# BlueBird_Sch.net
KiCad netlist of a schematic drawn in EAGLE
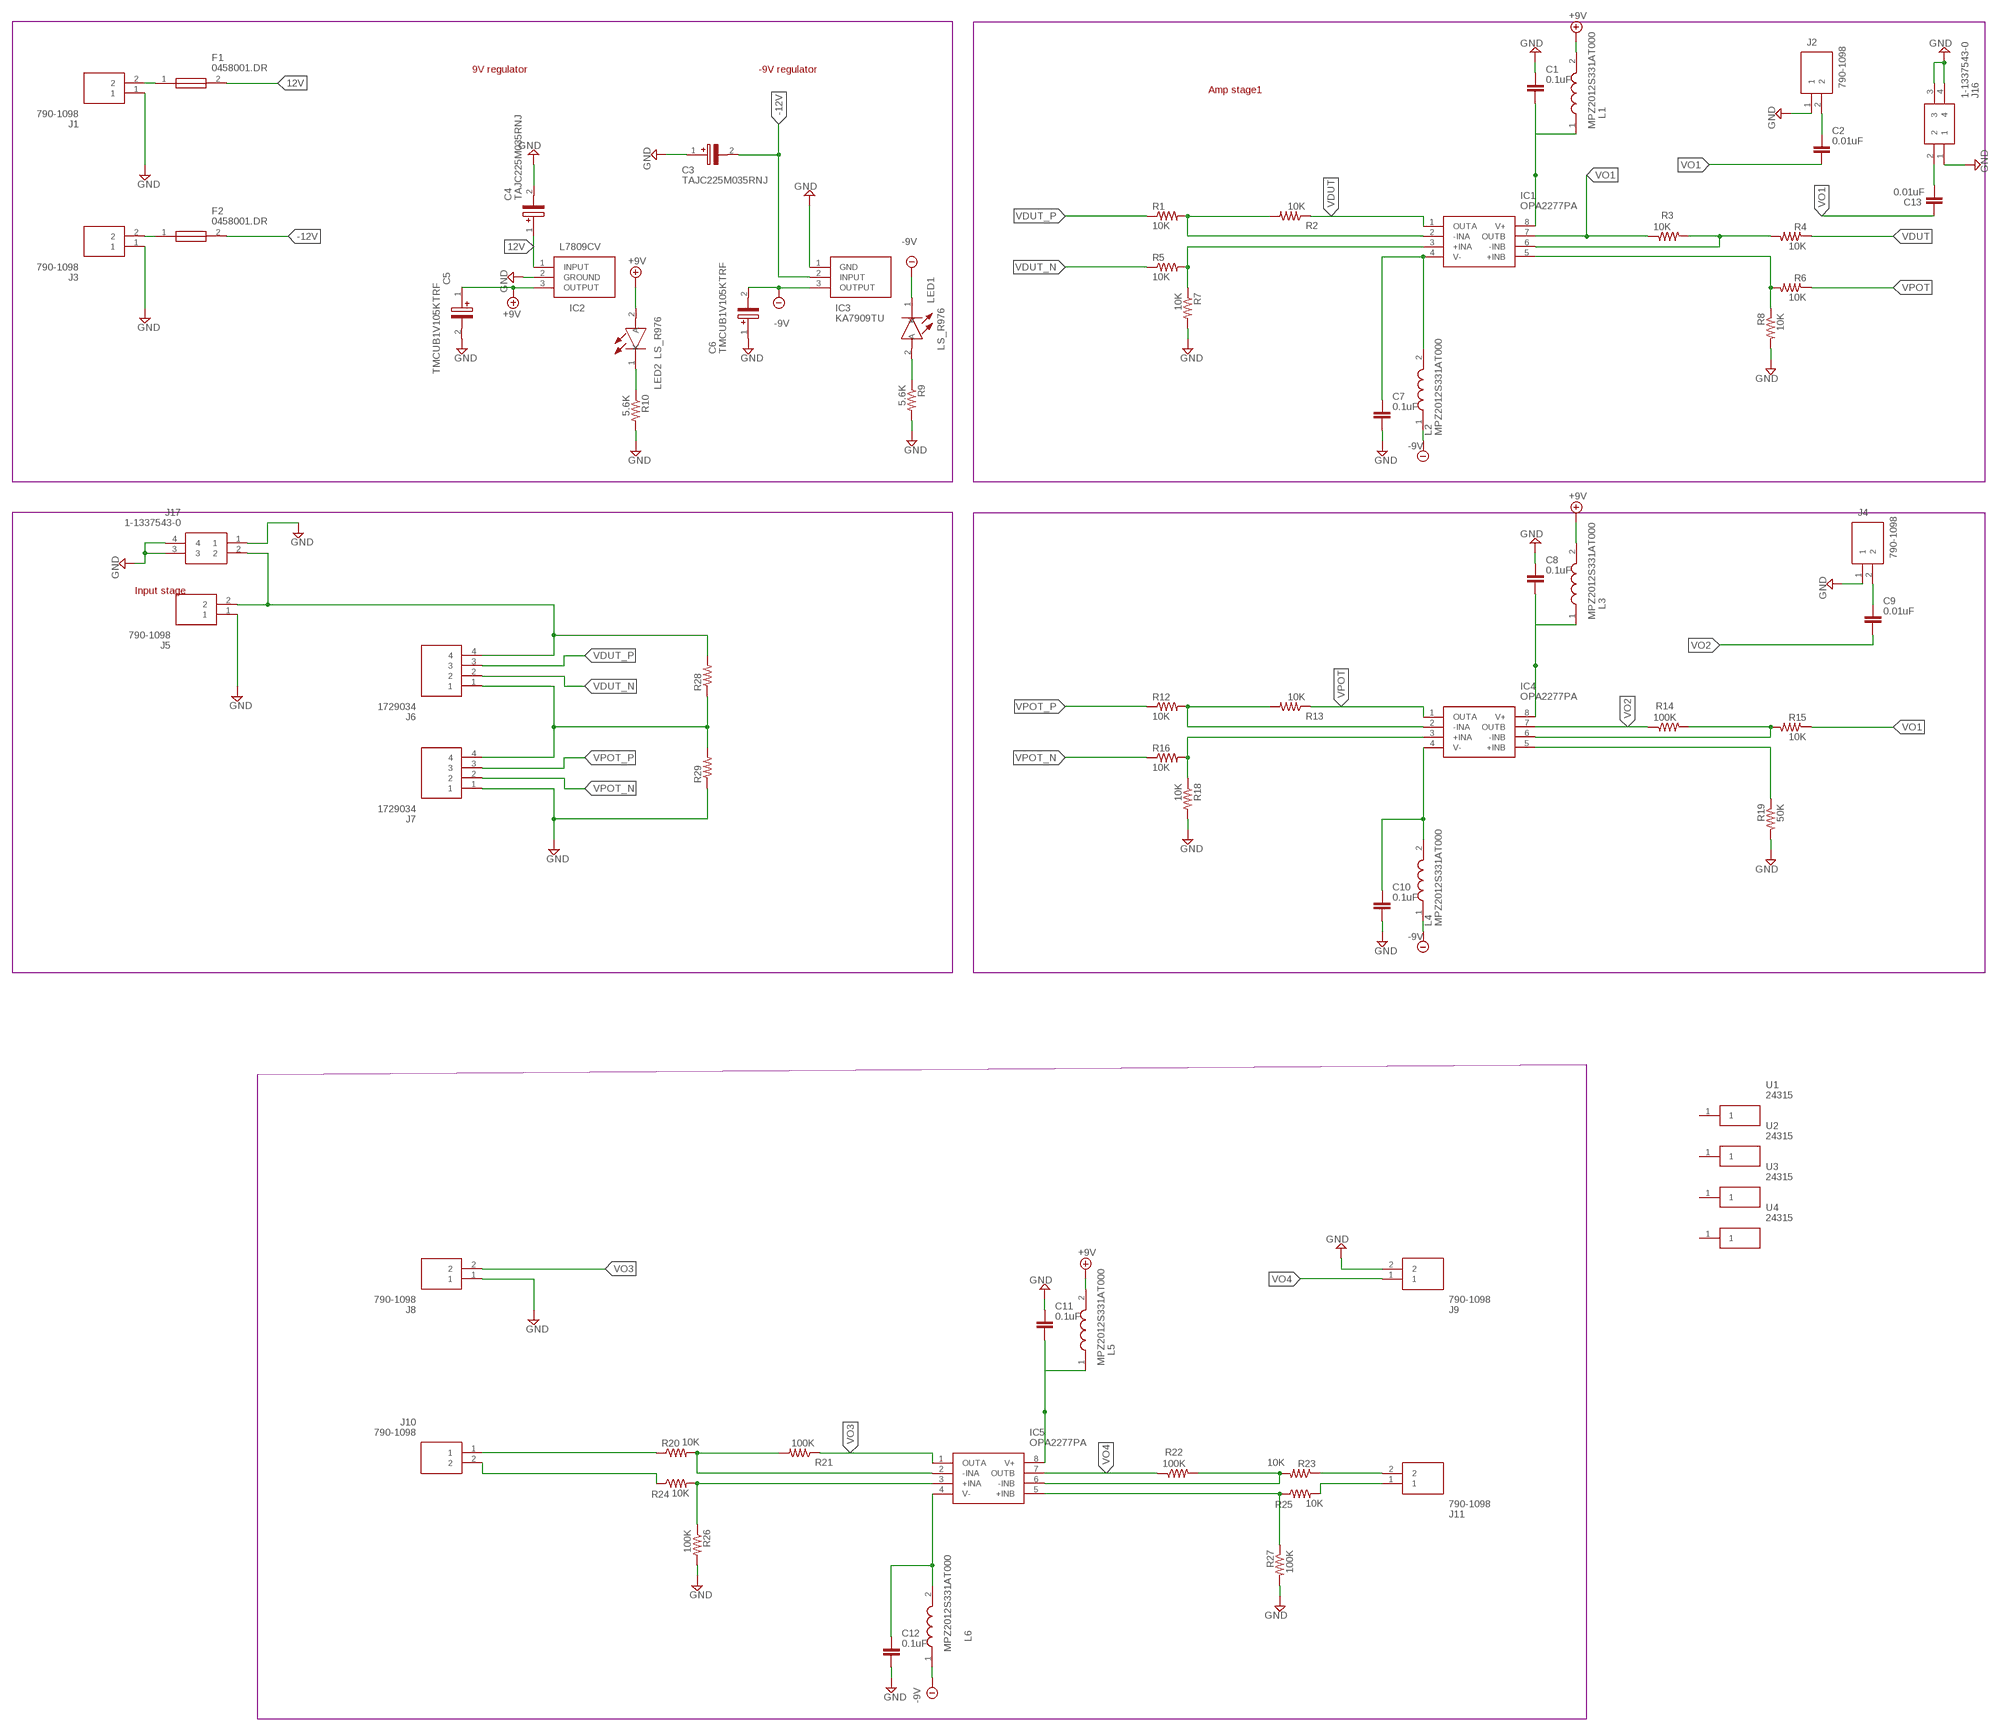
[diagram p0: schematic, sheet 1]

(export (version "E")
  (design (tool "Eeschema 10.0.6"))
  (components
    (comp (ref "C1")
      (value "0.1uF")
      (footprint "eagle-import:CAPC2012X110")
      (libsource (lib "eagle-import") (part "CCHIP-0805(2012-METRIC)_"))
    )
    (comp (ref "C2")
      (value "0.01uF")
      (footprint "eagle-import:CAPC2012X110")
      (libsource (lib "eagle-import") (part "CCHIP-0805(2012-METRIC)_"))
    )
    (comp (ref "C3")
      (value "TAJC225M035RNJ")
      (footprint "eagle-import:CAPPM6032X280N")
      (fields (field (name "RS_PART_NUMBER") "1364458P"))
      (libsource (lib "eagle-import") (part "TAJC225M035RNJ"))
    )
    (comp (ref "C4")
      (value "TAJC225M035RNJ")
      (footprint "eagle-import:CAPPM6032X280N")
      (fields (field (name "RS_PART_NUMBER") "1364458P"))
      (libsource (lib "eagle-import") (part "TAJC225M035RNJ"))
    )
    (comp (ref "C5")
      (value "TMCUB1V105KTRF")
      (footprint "eagle-import:CAPPM3528X120N")
      (fields (field (name "RS_PART_NUMBER") "1882061"))
      (libsource (lib "eagle-import") (part "TMCUB1V105KTRF"))
    )
    (comp (ref "C6")
      (value "TMCUB1V105KTRF")
      (footprint "eagle-import:CAPPM3528X120N")
      (fields (field (name "RS_PART_NUMBER") "1882061"))
      (libsource (lib "eagle-import") (part "TMCUB1V105KTRF"))
    )
    (comp (ref "C7")
      (value "0.1uF")
      (footprint "eagle-import:CAPC2012X110")
      (libsource (lib "eagle-import") (part "CCHIP-0805(2012-METRIC)_"))
    )
    (comp (ref "C8")
      (value "0.1uF")
      (footprint "eagle-import:CAPC2012X110")
      (libsource (lib "eagle-import") (part "CCHIP-0805(2012-METRIC)_"))
    )
    (comp (ref "C9")
      (value "0.01uF")
      (footprint "eagle-import:CAPC2012X110")
      (libsource (lib "eagle-import") (part "CCHIP-0805(2012-METRIC)_"))
    )
    (comp (ref "C10")
      (value "0.1uF")
      (footprint "eagle-import:CAPC2012X110")
      (libsource (lib "eagle-import") (part "CCHIP-0805(2012-METRIC)_"))
    )
    (comp (ref "C11")
      (value "0.1uF")
      (footprint "eagle-import:CAPC2012X110")
      (libsource (lib "eagle-import") (part "CCHIP-0805(2012-METRIC)_"))
    )
    (comp (ref "C12")
      (value "0.1uF")
      (footprint "eagle-import:CAPC2012X110")
      (libsource (lib "eagle-import") (part "CCHIP-0805(2012-METRIC)_"))
    )
    (comp (ref "C13")
      (value "0.01uF")
      (footprint "eagle-import:CAPC2012X110")
      (libsource (lib "eagle-import") (part "CCHIP-0805(2012-METRIC)_"))
    )
    (comp (ref "F1")
      (value "0458001.DR")
      (footprint "eagle-import:FUSC3215X58N")
      (libsource (lib "eagle-import") (part "0458001.DR"))
    )
    (comp (ref "F2")
      (value "0458001.DR")
      (footprint "eagle-import:FUSC3215X58N")
      (libsource (lib "eagle-import") (part "0458001.DR"))
    )
    (comp (ref "IC1")
      (value "OPA2277PA")
      (footprint "eagle-import:DIP794W53P254L959H508Q8N")
      (fields (field (name "RS_PART_NUMBER") "3071673P"))
      (libsource (lib "eagle-import") (part "OPA2277PA"))
    )
    (comp (ref "IC2")
      (value "L7809CV")
      (footprint "eagle-import:TO255P460X1020X2008-3P")
      (fields (field (name "RS_PART_NUMBER") "7140666P"))
      (libsource (lib "eagle-import") (part "L7809CV"))
    )
    (comp (ref "IC3")
      (value "KA7909TU")
      (footprint "eagle-import:TO254P470X1016X2019-3P")
      (fields (field (name "RS_PART_NUMBER") "7390552P"))
      (libsource (lib "eagle-import") (part "KA7909TU"))
    )
    (comp (ref "IC4")
      (value "OPA2277PA")
      (footprint "eagle-import:DIP794W53P254L959H508Q8N")
      (fields (field (name "RS_PART_NUMBER") "3071673P"))
      (libsource (lib "eagle-import") (part "OPA2277PA"))
    )
    (comp (ref "IC5")
      (value "OPA2277PA")
      (footprint "eagle-import:DIP794W53P254L959H508Q8N")
      (fields (field (name "RS_PART_NUMBER") "3071673P"))
      (libsource (lib "eagle-import") (part "OPA2277PA"))
    )
    (comp (ref "J1")
      (value "790-1098")
      (footprint "eagle-import:7901098")
      (libsource (lib "eagle-import") (part "790-1098"))
    )
    (comp (ref "J2")
      (value "790-1098")
      (footprint "eagle-import:7901098")
      (libsource (lib "eagle-import") (part "790-1098"))
    )
    (comp (ref "J3")
      (value "790-1098")
      (footprint "eagle-import:7901098")
      (libsource (lib "eagle-import") (part "790-1098"))
    )
    (comp (ref "J4")
      (value "790-1098")
      (footprint "eagle-import:7901098")
      (libsource (lib "eagle-import") (part "790-1098"))
    )
    (comp (ref "J5")
      (value "790-1098")
      (footprint "eagle-import:7901098")
      (libsource (lib "eagle-import") (part "790-1098"))
    )
    (comp (ref "J6")
      (value "1729034")
      (footprint "eagle-import:SHDR4W110P0X500_1X4_2000X810X1")
      (fields (field (name "RS_PART_NUMBER") "8020620"))
      (libsource (lib "eagle-import") (part "1729034"))
    )
    (comp (ref "J7")
      (value "1729034")
      (footprint "eagle-import:SHDR4W110P0X500_1X4_2000X810X1")
      (fields (field (name "RS_PART_NUMBER") "8020620"))
      (libsource (lib "eagle-import") (part "1729034"))
    )
    (comp (ref "J8")
      (value "790-1098")
      (footprint "eagle-import:7901098")
      (libsource (lib "eagle-import") (part "790-1098"))
    )
    (comp (ref "J9")
      (value "790-1098")
      (footprint "eagle-import:7901098")
      (libsource (lib "eagle-import") (part "790-1098"))
    )
    (comp (ref "J10")
      (value "790-1098")
      (footprint "eagle-import:7901098")
      (libsource (lib "eagle-import") (part "790-1098"))
    )
    (comp (ref "J11")
      (value "790-1098")
      (footprint "eagle-import:7901098")
      (libsource (lib "eagle-import") (part "790-1098"))
    )
    (comp (ref "J16")
      (value "1-1337543-0")
      (footprint "eagle-import:1-1337543-0")
      (fields (field (name "RS_PART_NUMBER") "5121225P"))
      (libsource (lib "eagle-import") (part "1-1337543-0"))
    )
    (comp (ref "J17")
      (value "1-1337543-0")
      (footprint "eagle-import:1-1337543-0")
      (fields (field (name "RS_PART_NUMBER") "5121225P"))
      (libsource (lib "eagle-import") (part "1-1337543-0"))
    )
    (comp (ref "L1")
      (value "MPZ2012S331AT000")
      (footprint "eagle-import:INDC2012X105N")
      (libsource (lib "eagle-import") (part "MPZ2012S331AT000"))
    )
    (comp (ref "L2")
      (value "MPZ2012S331AT000")
      (footprint "eagle-import:INDC2012X105N")
      (libsource (lib "eagle-import") (part "MPZ2012S331AT000"))
    )
    (comp (ref "L3")
      (value "MPZ2012S331AT000")
      (footprint "eagle-import:INDC2012X105N")
      (libsource (lib "eagle-import") (part "MPZ2012S331AT000"))
    )
    (comp (ref "L4")
      (value "MPZ2012S331AT000")
      (footprint "eagle-import:INDC2012X105N")
      (libsource (lib "eagle-import") (part "MPZ2012S331AT000"))
    )
    (comp (ref "L5")
      (value "MPZ2012S331AT000")
      (footprint "eagle-import:INDC2012X105N")
      (libsource (lib "eagle-import") (part "MPZ2012S331AT000"))
    )
    (comp (ref "L6")
      (value "MPZ2012S331AT000")
      (footprint "eagle-import:INDC2012X105N")
      (libsource (lib "eagle-import") (part "MPZ2012S331AT000"))
    )
    (comp (ref "LED1")
      (value "LS_R976")
      (footprint "eagle-import:LEDC2012X40N")
      (fields (field (name "MANUFACTURER_PART_NUMBER") "LS R976") (field (name "RS_PART_NUMBER") "4974804P"))
      (libsource (lib "eagle-import") (part "LS_R976"))
    )
    (comp (ref "LED2")
      (value "LS_R976")
      (footprint "eagle-import:LEDC2012X40N")
      (fields (field (name "MANUFACTURER_PART_NUMBER") "LS R976") (field (name "RS_PART_NUMBER") "4974804P"))
      (libsource (lib "eagle-import") (part "LS_R976"))
    )
    (comp (ref "R1")
      (value "10K")
      (footprint "eagle-import:R0805")
      (libsource (lib "eagle-import") (part "R-US_R0805"))
    )
    (comp (ref "R2")
      (value "10K")
      (footprint "eagle-import:R0805")
      (libsource (lib "eagle-import") (part "R-US_R0805"))
    )
    (comp (ref "R3")
      (value "10K")
      (footprint "eagle-import:R0805")
      (libsource (lib "eagle-import") (part "R-US_R0805"))
    )
    (comp (ref "R4")
      (value "10K")
      (footprint "eagle-import:R0805")
      (libsource (lib "eagle-import") (part "R-US_R0805"))
    )
    (comp (ref "R5")
      (value "10K")
      (footprint "eagle-import:R0805")
      (libsource (lib "eagle-import") (part "R-US_R0805"))
    )
    (comp (ref "R6")
      (value "10K")
      (footprint "eagle-import:R0805")
      (libsource (lib "eagle-import") (part "R-US_R0805"))
    )
    (comp (ref "R7")
      (value "10K")
      (footprint "eagle-import:R0805")
      (libsource (lib "eagle-import") (part "R-US_R0805"))
    )
    (comp (ref "R8")
      (value "10K")
      (footprint "eagle-import:R0805")
      (libsource (lib "eagle-import") (part "R-US_R0805"))
    )
    (comp (ref "R9")
      (value "5.6K")
      (footprint "eagle-import:R0805")
      (libsource (lib "eagle-import") (part "R-US_R0805"))
    )
    (comp (ref "R10")
      (value "5.6K")
      (footprint "eagle-import:R0805")
      (libsource (lib "eagle-import") (part "R-US_R0805"))
    )
    (comp (ref "R12")
      (value "10K")
      (footprint "eagle-import:R0805")
      (libsource (lib "eagle-import") (part "R-US_R0805"))
    )
    (comp (ref "R13")
      (value "10K")
      (footprint "eagle-import:R0805")
      (libsource (lib "eagle-import") (part "R-US_R0805"))
    )
    (comp (ref "R14")
      (value "100K")
      (footprint "eagle-import:R0805")
      (libsource (lib "eagle-import") (part "R-US_R0805"))
    )
    (comp (ref "R15")
      (value "10K")
      (footprint "eagle-import:R0805")
      (libsource (lib "eagle-import") (part "R-US_R0805"))
    )
    (comp (ref "R16")
      (value "10K")
      (footprint "eagle-import:R0805")
      (libsource (lib "eagle-import") (part "R-US_R0805"))
    )
    (comp (ref "R18")
      (value "10K")
      (footprint "eagle-import:R0805")
      (libsource (lib "eagle-import") (part "R-US_R0805"))
    )
    (comp (ref "R19")
      (value "50K")
      (footprint "eagle-import:R0805")
      (libsource (lib "eagle-import") (part "R-US_R0805"))
    )
    (comp (ref "R20")
      (value "10K")
      (footprint "eagle-import:R0805")
      (libsource (lib "eagle-import") (part "R-US_R0805"))
    )
    (comp (ref "R21")
      (value "100K")
      (footprint "eagle-import:R0805")
      (libsource (lib "eagle-import") (part "R-US_R0805"))
    )
    (comp (ref "R22")
      (value "100K")
      (footprint "eagle-import:R0805")
      (libsource (lib "eagle-import") (part "R-US_R0805"))
    )
    (comp (ref "R23")
      (value "10K")
      (footprint "eagle-import:R0805")
      (libsource (lib "eagle-import") (part "R-US_R0805"))
    )
    (comp (ref "R24")
      (value "10K")
      (footprint "eagle-import:R0805")
      (libsource (lib "eagle-import") (part "R-US_R0805"))
    )
    (comp (ref "R25")
      (value "10K")
      (footprint "eagle-import:R0805")
      (libsource (lib "eagle-import") (part "R-US_R0805"))
    )
    (comp (ref "R26")
      (value "100K")
      (footprint "eagle-import:R0805")
      (libsource (lib "eagle-import") (part "R-US_R0805"))
    )
    (comp (ref "R27")
      (value "100K")
      (footprint "eagle-import:R0805")
      (libsource (lib "eagle-import") (part "R-US_R0805"))
    )
    (comp (ref "R28")
      (value "R-US_R1206")
      (footprint "eagle-import:R1206")
      (libsource (lib "eagle-import") (part "R-US_R1206"))
    )
    (comp (ref "R29")
      (value "R-US_R1206")
      (footprint "eagle-import:R1206")
      (libsource (lib "eagle-import") (part "R-US_R1206"))
    )
    (comp (ref "U1")
      (value "24315")
      (footprint "eagle-import:24315")
      (libsource (lib "eagle-import") (part "24315"))
    )
    (comp (ref "U2")
      (value "24315")
      (footprint "eagle-import:24315")
      (libsource (lib "eagle-import") (part "24315"))
    )
    (comp (ref "U3")
      (value "24315")
      (footprint "eagle-import:24315")
      (libsource (lib "eagle-import") (part "24315"))
    )
    (comp (ref "U4")
      (value "24315")
      (footprint "eagle-import:24315")
      (libsource (lib "eagle-import") (part "24315"))
    )
  )
  (nets
    (net (code "1") (name "+9V") (class "Default")
      (node (ref "C5") (pin "1") (pinfunction "+_1") (pintype "bidirectional"))
      (node (ref "IC2") (pin "3") (pinfunction "OUTPUT_3") (pintype "bidirectional"))
      (node (ref "L1") (pin "2") (pinfunction "2_2") (pintype "bidirectional"))
      (node (ref "L3") (pin "2") (pinfunction "2_2") (pintype "bidirectional"))
      (node (ref "L5") (pin "2") (pinfunction "2_2") (pintype "bidirectional"))
      (node (ref "LED2") (pin "2") (pinfunction "A_2") (pintype "bidirectional"))
    )
    (net (code "2") (name "-9V") (class "Default")
      (node (ref "C6") (pin "2") (pinfunction "-_2") (pintype "bidirectional"))
      (node (ref "IC3") (pin "3") (pinfunction "OUTPUT_3") (pintype "bidirectional"))
      (node (ref "L2") (pin "1") (pinfunction "1_1") (pintype "bidirectional"))
      (node (ref "L4") (pin "1") (pinfunction "1_1") (pintype "bidirectional"))
      (node (ref "L6") (pin "1") (pinfunction "1_1") (pintype "bidirectional"))
      (node (ref "LED1") (pin "1") (pinfunction "K_1") (pintype "bidirectional"))
    )
    (net (code "3") (name "-12V") (class "Default")
      (node (ref "C3") (pin "2") (pinfunction "-_2") (pintype "bidirectional"))
      (node (ref "F2") (pin "2") (pinfunction "2_2") (pintype "bidirectional"))
      (node (ref "IC3") (pin "2") (pinfunction "INPUT_2") (pintype "bidirectional"))
    )
    (net (code "4") (name "12V") (class "Default")
      (node (ref "C4") (pin "1") (pinfunction "+_1") (pintype "bidirectional"))
      (node (ref "F1") (pin "2") (pinfunction "2_2") (pintype "bidirectional"))
      (node (ref "IC2") (pin "1") (pinfunction "INPUT_1") (pintype "bidirectional"))
    )
    (net (code "5") (name "GND") (class "Default")
      (node (ref "C1") (pin "1") (pinfunction "1_1") (pintype "passive"))
      (node (ref "C10") (pin "2") (pinfunction "2_2") (pintype "passive"))
      (node (ref "C11") (pin "1") (pinfunction "1_1") (pintype "passive"))
      (node (ref "C12") (pin "2") (pinfunction "2_2") (pintype "passive"))
      (node (ref "C3") (pin "1") (pinfunction "+_1") (pintype "bidirectional"))
      (node (ref "C4") (pin "2") (pinfunction "-_2") (pintype "bidirectional"))
      (node (ref "C5") (pin "2") (pinfunction "-_2") (pintype "bidirectional"))
      (node (ref "C6") (pin "1") (pinfunction "+_1") (pintype "bidirectional"))
      (node (ref "C7") (pin "2") (pinfunction "2_2") (pintype "passive"))
      (node (ref "C8") (pin "1") (pinfunction "1_1") (pintype "passive"))
      (node (ref "IC2") (pin "2") (pinfunction "GROUND_2") (pintype "bidirectional"))
      (node (ref "IC3") (pin "1") (pinfunction "GND_1") (pintype "bidirectional"))
      (node (ref "J1") (pin "1") (pinfunction "1_1") (pintype "bidirectional"))
      (node (ref "J16") (pin "1") (pinfunction "1_1") (pintype "bidirectional"))
      (node (ref "J16") (pin "3") (pinfunction "3_3") (pintype "bidirectional"))
      (node (ref "J16") (pin "4") (pinfunction "4_4") (pintype "bidirectional"))
      (node (ref "J17") (pin "1") (pinfunction "1_1") (pintype "bidirectional"))
      (node (ref "J17") (pin "3") (pinfunction "3_3") (pintype "bidirectional"))
      (node (ref "J17") (pin "4") (pinfunction "4_4") (pintype "bidirectional"))
      (node (ref "J2") (pin "1") (pinfunction "1_1") (pintype "bidirectional"))
      (node (ref "J3") (pin "1") (pinfunction "1_1") (pintype "bidirectional"))
      (node (ref "J4") (pin "1") (pinfunction "1_1") (pintype "bidirectional"))
      (node (ref "J5") (pin "1") (pinfunction "1_1") (pintype "bidirectional"))
      (node (ref "J7") (pin "1") (pinfunction "1_1") (pintype "bidirectional"))
      (node (ref "J8") (pin "1") (pinfunction "1_1") (pintype "bidirectional"))
      (node (ref "J9") (pin "2") (pinfunction "2_2") (pintype "bidirectional"))
      (node (ref "R10") (pin "2") (pinfunction "2_2") (pintype "passive"))
      (node (ref "R18") (pin "2") (pinfunction "2_2") (pintype "passive"))
      (node (ref "R19") (pin "2") (pinfunction "2_2") (pintype "passive"))
      (node (ref "R26") (pin "2") (pinfunction "2_2") (pintype "passive"))
      (node (ref "R27") (pin "2") (pinfunction "2_2") (pintype "passive"))
      (node (ref "R29") (pin "1") (pinfunction "1_1") (pintype "passive"))
      (node (ref "R7") (pin "2") (pinfunction "2_2") (pintype "passive"))
      (node (ref "R8") (pin "2") (pinfunction "2_2") (pintype "passive"))
      (node (ref "R9") (pin "2") (pinfunction "2_2") (pintype "passive"))
    )
    (net (code "6") (name "Net-(C2-Pad1)") (class "Default")
      (node (ref "C2") (pin "1") (pinfunction "1_1") (pintype "passive"))
      (node (ref "J2") (pin "2") (pinfunction "2_2") (pintype "bidirectional"))
    )
    (net (code "7") (name "Net-(C9-Pad1)") (class "Default")
      (node (ref "C9") (pin "1") (pinfunction "1_1") (pintype "passive"))
      (node (ref "J4") (pin "2") (pinfunction "2_2") (pintype "bidirectional"))
    )
    (net (code "8") (name "Net-(C13-Pad1)") (class "Default")
      (node (ref "C13") (pin "1") (pinfunction "1_1") (pintype "passive"))
      (node (ref "J16") (pin "2") (pinfunction "2_2") (pintype "bidirectional"))
    )
    (net (code "9") (name "Net-(F1-Pad1)") (class "Default")
      (node (ref "F1") (pin "1") (pinfunction "1_1") (pintype "bidirectional"))
      (node (ref "J1") (pin "2") (pinfunction "2_2") (pintype "bidirectional"))
    )
    (net (code "10") (name "Net-(F2-Pad1)") (class "Default")
      (node (ref "F2") (pin "1") (pinfunction "1_1") (pintype "bidirectional"))
      (node (ref "J3") (pin "2") (pinfunction "2_2") (pintype "bidirectional"))
    )
    (net (code "11") (name "Net-(IC1-+INA)") (class "Default")
      (node (ref "IC1") (pin "3") (pinfunction "+INA_3") (pintype "input"))
      (node (ref "R5") (pin "2") (pinfunction "2_2") (pintype "passive"))
      (node (ref "R7") (pin "1") (pinfunction "1_1") (pintype "passive"))
    )
    (net (code "12") (name "Net-(IC1-+INB)") (class "Default")
      (node (ref "IC1") (pin "5") (pinfunction "+INB_5") (pintype "input"))
      (node (ref "R6") (pin "2") (pinfunction "2_2") (pintype "passive"))
      (node (ref "R8") (pin "1") (pinfunction "1_1") (pintype "passive"))
    )
    (net (code "13") (name "Net-(IC1--INA)") (class "Default")
      (node (ref "IC1") (pin "2") (pinfunction "-INA_2") (pintype "input"))
      (node (ref "R1") (pin "2") (pinfunction "2_2") (pintype "passive"))
      (node (ref "R2") (pin "2") (pinfunction "2_2") (pintype "passive"))
    )
    (net (code "14") (name "Net-(IC1--INB)") (class "Default")
      (node (ref "IC1") (pin "6") (pinfunction "-INB_6") (pintype "input"))
      (node (ref "R3") (pin "2") (pinfunction "2_2") (pintype "passive"))
      (node (ref "R4") (pin "2") (pinfunction "2_2") (pintype "passive"))
    )
    (net (code "15") (name "Net-(IC1-V+)") (class "Default")
      (node (ref "C1") (pin "2") (pinfunction "2_2") (pintype "passive"))
      (node (ref "IC1") (pin "8") (pinfunction "V+_8") (pintype "power_in"))
      (node (ref "L1") (pin "1") (pinfunction "1_1") (pintype "bidirectional"))
    )
    (net (code "16") (name "Net-(IC1-V-)") (class "Default")
      (node (ref "C7") (pin "1") (pinfunction "1_1") (pintype "passive"))
      (node (ref "IC1") (pin "4") (pinfunction "V-_4") (pintype "power_in"))
      (node (ref "L2") (pin "2") (pinfunction "2_2") (pintype "bidirectional"))
    )
    (net (code "17") (name "Net-(IC4-+INA)") (class "Default")
      (node (ref "IC4") (pin "3") (pinfunction "+INA_3") (pintype "input"))
      (node (ref "R16") (pin "2") (pinfunction "2_2") (pintype "passive"))
      (node (ref "R18") (pin "1") (pinfunction "1_1") (pintype "passive"))
    )
    (net (code "18") (name "Net-(IC4-+INB)") (class "Default")
      (node (ref "IC4") (pin "5") (pinfunction "+INB_5") (pintype "input"))
      (node (ref "R19") (pin "1") (pinfunction "1_1") (pintype "passive"))
    )
    (net (code "19") (name "Net-(IC4--INA)") (class "Default")
      (node (ref "IC4") (pin "2") (pinfunction "-INA_2") (pintype "input"))
      (node (ref "R12") (pin "2") (pinfunction "2_2") (pintype "passive"))
      (node (ref "R13") (pin "2") (pinfunction "2_2") (pintype "passive"))
    )
    (net (code "20") (name "Net-(IC4--INB)") (class "Default")
      (node (ref "IC4") (pin "6") (pinfunction "-INB_6") (pintype "input"))
      (node (ref "R14") (pin "2") (pinfunction "2_2") (pintype "passive"))
      (node (ref "R15") (pin "2") (pinfunction "2_2") (pintype "passive"))
    )
    (net (code "21") (name "Net-(IC4-V+)") (class "Default")
      (node (ref "C8") (pin "2") (pinfunction "2_2") (pintype "passive"))
      (node (ref "IC4") (pin "8") (pinfunction "V+_8") (pintype "power_in"))
      (node (ref "L3") (pin "1") (pinfunction "1_1") (pintype "bidirectional"))
    )
    (net (code "22") (name "Net-(IC4-V-)") (class "Default")
      (node (ref "C10") (pin "1") (pinfunction "1_1") (pintype "passive"))
      (node (ref "IC4") (pin "4") (pinfunction "V-_4") (pintype "power_in"))
      (node (ref "L4") (pin "2") (pinfunction "2_2") (pintype "bidirectional"))
    )
    (net (code "23") (name "Net-(IC5-+INA)") (class "Default")
      (node (ref "IC5") (pin "3") (pinfunction "+INA_3") (pintype "input"))
      (node (ref "R24") (pin "2") (pinfunction "2_2") (pintype "passive"))
      (node (ref "R26") (pin "1") (pinfunction "1_1") (pintype "passive"))
    )
    (net (code "24") (name "Net-(IC5-+INB)") (class "Default")
      (node (ref "IC5") (pin "5") (pinfunction "+INB_5") (pintype "input"))
      (node (ref "R25") (pin "1") (pinfunction "1_1") (pintype "passive"))
      (node (ref "R27") (pin "1") (pinfunction "1_1") (pintype "passive"))
    )
    (net (code "25") (name "Net-(IC5--INA)") (class "Default")
      (node (ref "IC5") (pin "2") (pinfunction "-INA_2") (pintype "input"))
      (node (ref "R20") (pin "2") (pinfunction "2_2") (pintype "passive"))
      (node (ref "R21") (pin "2") (pinfunction "2_2") (pintype "passive"))
    )
    (net (code "26") (name "Net-(IC5--INB)") (class "Default")
      (node (ref "IC5") (pin "6") (pinfunction "-INB_6") (pintype "input"))
      (node (ref "R22") (pin "2") (pinfunction "2_2") (pintype "passive"))
      (node (ref "R23") (pin "2") (pinfunction "2_2") (pintype "passive"))
    )
    (net (code "27") (name "Net-(IC5-V+)") (class "Default")
      (node (ref "C11") (pin "2") (pinfunction "2_2") (pintype "passive"))
      (node (ref "IC5") (pin "8") (pinfunction "V+_8") (pintype "power_in"))
      (node (ref "L5") (pin "1") (pinfunction "1_1") (pintype "bidirectional"))
    )
    (net (code "28") (name "Net-(IC5-V-)") (class "Default")
      (node (ref "C12") (pin "1") (pinfunction "1_1") (pintype "passive"))
      (node (ref "IC5") (pin "4") (pinfunction "V-_4") (pintype "power_in"))
      (node (ref "L6") (pin "2") (pinfunction "2_2") (pintype "bidirectional"))
    )
    (net (code "29") (name "Net-(J6-Pad1)") (class "Default")
      (node (ref "J6") (pin "1") (pinfunction "1_1") (pintype "bidirectional"))
      (node (ref "J7") (pin "4") (pinfunction "4_4") (pintype "bidirectional"))
      (node (ref "R28") (pin "1") (pinfunction "1_1") (pintype "passive"))
      (node (ref "R29") (pin "2") (pinfunction "2_2") (pintype "passive"))
    )
    (net (code "30") (name "Net-(J10-Pad1)") (class "Default")
      (node (ref "J10") (pin "1") (pinfunction "1_1") (pintype "bidirectional"))
      (node (ref "R20") (pin "1") (pinfunction "1_1") (pintype "passive"))
    )
    (net (code "31") (name "Net-(J10-Pad2)") (class "Default")
      (node (ref "J10") (pin "2") (pinfunction "2_2") (pintype "bidirectional"))
      (node (ref "R24") (pin "1") (pinfunction "1_1") (pintype "passive"))
    )
    (net (code "32") (name "Net-(J11-Pad1)") (class "Default")
      (node (ref "J11") (pin "1") (pinfunction "1_1") (pintype "bidirectional"))
      (node (ref "R25") (pin "2") (pinfunction "2_2") (pintype "passive"))
    )
    (net (code "33") (name "Net-(J11-Pad2)") (class "Default")
      (node (ref "J11") (pin "2") (pinfunction "2_2") (pintype "bidirectional"))
      (node (ref "R23") (pin "1") (pinfunction "1_1") (pintype "passive"))
    )
    (net (code "34") (name "Net-(J17-Pad2)") (class "Default")
      (node (ref "J17") (pin "2") (pinfunction "2_2") (pintype "bidirectional"))
      (node (ref "J5") (pin "2") (pinfunction "2_2") (pintype "bidirectional"))
      (node (ref "J6") (pin "4") (pinfunction "4_4") (pintype "bidirectional"))
      (node (ref "R28") (pin "2") (pinfunction "2_2") (pintype "passive"))
    )
    (net (code "35") (name "Net-(LED1-A)") (class "Default")
      (node (ref "LED1") (pin "2") (pinfunction "A_2") (pintype "bidirectional"))
      (node (ref "R9") (pin "1") (pinfunction "1_1") (pintype "passive"))
    )
    (net (code "36") (name "Net-(LED2-K)") (class "Default")
      (node (ref "LED2") (pin "1") (pinfunction "K_1") (pintype "bidirectional"))
      (node (ref "R10") (pin "1") (pinfunction "1_1") (pintype "passive"))
    )
    (net (code "37") (name "VDUT") (class "Default")
      (node (ref "IC1") (pin "1") (pinfunction "OUTA_1") (pintype "output"))
      (node (ref "R2") (pin "1") (pinfunction "1_1") (pintype "passive"))
      (node (ref "R4") (pin "1") (pinfunction "1_1") (pintype "passive"))
    )
    (net (code "38") (name "VDUT_N") (class "Default")
      (node (ref "J6") (pin "2") (pinfunction "2_2") (pintype "bidirectional"))
      (node (ref "R5") (pin "1") (pinfunction "1_1") (pintype "passive"))
    )
    (net (code "39") (name "VDUT_P") (class "Default")
      (node (ref "J6") (pin "3") (pinfunction "3_3") (pintype "bidirectional"))
      (node (ref "R1") (pin "1") (pinfunction "1_1") (pintype "passive"))
    )
    (net (code "40") (name "VO1") (class "Default")
      (node (ref "C13") (pin "2") (pinfunction "2_2") (pintype "passive"))
      (node (ref "C2") (pin "2") (pinfunction "2_2") (pintype "passive"))
      (node (ref "IC1") (pin "7") (pinfunction "OUTB_7") (pintype "output"))
      (node (ref "R15") (pin "1") (pinfunction "1_1") (pintype "passive"))
      (node (ref "R3") (pin "1") (pinfunction "1_1") (pintype "passive"))
    )
    (net (code "41") (name "VO2") (class "Default")
      (node (ref "C9") (pin "2") (pinfunction "2_2") (pintype "passive"))
      (node (ref "IC4") (pin "7") (pinfunction "OUTB_7") (pintype "output"))
      (node (ref "R14") (pin "1") (pinfunction "1_1") (pintype "passive"))
    )
    (net (code "42") (name "VO3") (class "Default")
      (node (ref "IC5") (pin "1") (pinfunction "OUTA_1") (pintype "output"))
      (node (ref "J8") (pin "2") (pinfunction "2_2") (pintype "bidirectional"))
      (node (ref "R21") (pin "1") (pinfunction "1_1") (pintype "passive"))
    )
    (net (code "43") (name "VO4") (class "Default")
      (node (ref "IC5") (pin "7") (pinfunction "OUTB_7") (pintype "output"))
      (node (ref "J9") (pin "1") (pinfunction "1_1") (pintype "bidirectional"))
      (node (ref "R22") (pin "1") (pinfunction "1_1") (pintype "passive"))
    )
    (net (code "44") (name "VPOT") (class "Default")
      (node (ref "IC4") (pin "1") (pinfunction "OUTA_1") (pintype "output"))
      (node (ref "R13") (pin "1") (pinfunction "1_1") (pintype "passive"))
      (node (ref "R6") (pin "1") (pinfunction "1_1") (pintype "passive"))
    )
    (net (code "45") (name "VPOT_N") (class "Default")
      (node (ref "J7") (pin "2") (pinfunction "2_2") (pintype "bidirectional"))
      (node (ref "R16") (pin "1") (pinfunction "1_1") (pintype "passive"))
    )
    (net (code "46") (name "VPOT_P") (class "Default")
      (node (ref "J7") (pin "3") (pinfunction "3_3") (pintype "bidirectional"))
      (node (ref "R12") (pin "1") (pinfunction "1_1") (pintype "passive"))
    )
    (net (code "47") (name "unconnected-(U1-Pad1)") (class "Default")
      (node (ref "U1") (pin "1") (pinfunction "1_1") (pintype "bidirectional"))
    )
    (net (code "48") (name "unconnected-(U2-Pad1)") (class "Default")
      (node (ref "U2") (pin "1") (pinfunction "1_1") (pintype "bidirectional"))
    )
    (net (code "49") (name "unconnected-(U3-Pad1)") (class "Default")
      (node (ref "U3") (pin "1") (pinfunction "1_1") (pintype "bidirectional"))
    )
    (net (code "50") (name "unconnected-(U4-Pad1)") (class "Default")
      (node (ref "U4") (pin "1") (pinfunction "1_1") (pintype "bidirectional"))
    )
  )
)
